# Half_bridge_drivers.net
KiCad netlist of a schematic drawn in Altium Designer
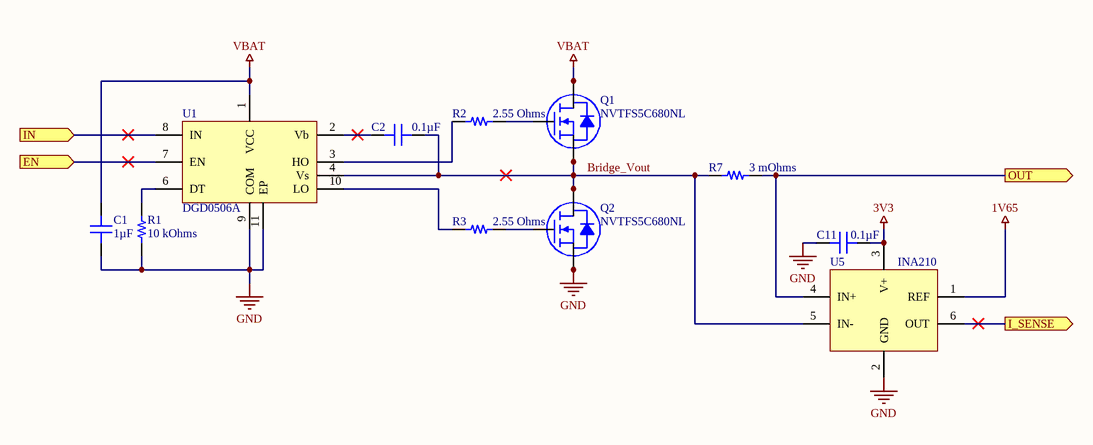
[diagram p0: Half_bridge_drivers.SchDoc]

(export (version "E")
  (design (tool "Eeschema 10.0.6"))
  (components
    (comp (ref "C1")
      (value "1µF")
      (footprint "CAP 0603_1608")
      (description "CAP CER 1UF 25V X7R 0603")
      (fields
        (field (name "PART NUMBER") "GCJ188R71E105KA01D")
        (field (name "MANUFACTURER") "Murata Electronics")
      )
      (libsource (lib "Celestial Altium Library - altium_library") (part "Capacitor"))
    )
    (comp (ref "C2")
      (value "0.1µF")
      (footprint "CAP 0603_1608")
      (description "CAP CER 0.1UF 100V 0603 EPOXY")
      (fields
        (field (name "PART NUMBER") "GCG188R92A104KA03D")
        (field (name "MANUFACTURER") "Murata Electronics")
      )
      (libsource (lib "Celestial Altium Library - altium_library") (part "Capacitor"))
    )
    (comp (ref "C11")
      (value "0.1µF")
      (footprint "CAP 0603_1608")
      (description "CAP CER 0.1UF 100V 0603 EPOXY")
      (fields
        (field (name "PART NUMBER") "GCG188R92A104KA03D")
        (field (name "MANUFACTURER") "Murata Electronics")
      )
      (libsource (lib "Celestial Altium Library - altium_library") (part "Capacitor"))
    )
    (comp (ref "Q1")
      (value "NVTFS5C680NL")
      (footprint "NVTFS015N04CTAG")
      (libsource (lib "IC") (part "NVTFS5C680NL"))
    )
    (comp (ref "Q2")
      (value "NVTFS5C680NL")
      (footprint "NVTFS015N04CTAG")
      (libsource (lib "IC") (part "NVTFS5C680NL"))
    )
    (comp (ref "R1")
      (value "10 kOhms")
      (footprint "RES 0603_1608")
      (description "RES 10K OHM 0.1% 1/16W 0603")
      (fields
        (field (name "PART NUMBER") "RNCS0603BKE10K0")
        (field (name "MANUFACTURER") "Stackpole Electronics Inc")
      )
      (libsource (lib "Celestial Altium Library - altium_library") (part "Resistor"))
    )
    (comp (ref "R2")
      (value "2.55 Ohms")
      (footprint "RES 0603_1608")
      (description "RES SMD 2.55 OHM 1% 1/10W 0603")
      (fields (field (name "PART NUMBER") "CRCW06032R55FKEA") (field (name "MANUFACTURER") "Vishay Dale"))
      (libsource (lib "Celestial Altium Library - altium_library") (part "Resistor"))
    )
    (comp (ref "R3")
      (value "2.55 Ohms")
      (footprint "RES 0603_1608")
      (description "RES SMD 2.55 OHM 1% 1/10W 0603")
      (fields (field (name "PART NUMBER") "CRCW06032R55FKEA") (field (name "MANUFACTURER") "Vishay Dale"))
      (libsource (lib "Celestial Altium Library - altium_library") (part "Resistor"))
    )
    (comp (ref "R7")
      (value "3 mOhms")
      (footprint "STACKPOLE CSR0603")
      (description "RES SHUNT, 0603, 0.003 OHM, 1%,")
      (fields
        (field (name "PART NUMBER") "CSS0603FT3L00")
        (field (name "MANUFACTURER") "Stackpole Electronics Inc")
      )
      (libsource (lib "Celestial Altium Library - altium_library") (part "Resistor"))
    )
    (comp (ref "U1")
      (value "DGD0506A")
      (footprint "10-WDFN3030")
      (description "Half Bridge driver - N FET")
      (libsource (lib "IC") (part "DGD0506A"))
    )
    (comp (ref "U5")
      (value "INA210")
      (footprint "TI SC70-6 DCK")
      (description "Current sense amplifier")
      (libsource (lib "IC") (part "INA210"))
    )
  )
  (nets
    (net (code "1") (name "/Bridge_Vout") (class "Default")
      (node (ref "C2") (pin "1") (pinfunction "1_1") (pintype "passive"))
      (node (ref "Q1") (pin "1") (pinfunction "S_1") (pintype "passive"))
      (node (ref "Q1") (pin "2") (pinfunction "S_2") (pintype "passive"))
      (node (ref "Q1") (pin "3") (pinfunction "S_3") (pintype "passive"))
      (node (ref "Q2") (pin "5") (pinfunction "D_5") (pintype "passive"))
      (node (ref "Q2") (pin "6") (pinfunction "D_6") (pintype "passive"))
      (node (ref "Q2") (pin "7") (pinfunction "D_7") (pintype "passive"))
      (node (ref "Q2") (pin "8") (pinfunction "D_8") (pintype "passive"))
      (node (ref "R7") (pin "1") (pinfunction "1_1") (pintype "passive"))
      (node (ref "U1") (pin "4") (pinfunction "Vs_4") (pintype "passive"))
      (node (ref "U5") (pin "5") (pinfunction "IN-_5") (pintype "passive"))
    )
    (net (code "2") (name "/EN") (class "Default")
      (node (ref "U1") (pin "7") (pinfunction "EN_7") (pintype "passive"))
    )
    (net (code "3") (name "/IN") (class "Default")
      (node (ref "U1") (pin "8") (pinfunction "IN_8") (pintype "passive"))
    )
    (net (code "4") (name "/I_SENSE") (class "Default")
      (node (ref "U5") (pin "6") (pinfunction "OUT_6") (pintype "passive"))
    )
    (net (code "5") (name "/OUT") (class "Default")
      (node (ref "R7") (pin "2") (pinfunction "2_2") (pintype "passive"))
      (node (ref "U5") (pin "4") (pinfunction "IN+_4") (pintype "passive"))
    )
    (net (code "6") (name "1V65") (class "Default")
      (node (ref "U5") (pin "1") (pinfunction "REF_1") (pintype "passive"))
    )
    (net (code "7") (name "3V3") (class "Default")
      (node (ref "C11") (pin "2") (pinfunction "2_2") (pintype "passive"))
      (node (ref "U5") (pin "3") (pinfunction "V+_3") (pintype "passive"))
    )
    (net (code "8") (name "GND") (class "Default")
      (node (ref "C1") (pin "1") (pinfunction "1_1") (pintype "passive"))
      (node (ref "C11") (pin "1") (pinfunction "1_1") (pintype "passive"))
      (node (ref "Q2") (pin "1") (pinfunction "S_1") (pintype "passive"))
      (node (ref "Q2") (pin "2") (pinfunction "S_2") (pintype "passive"))
      (node (ref "Q2") (pin "3") (pinfunction "S_3") (pintype "passive"))
      (node (ref "R1") (pin "2") (pinfunction "2_2") (pintype "passive"))
      (node (ref "U1") (pin "11") (pinfunction "EP_11") (pintype "passive"))
      (node (ref "U1") (pin "9") (pinfunction "COM_9") (pintype "passive"))
      (node (ref "U5") (pin "2") (pinfunction "GND_2") (pintype "passive"))
    )
    (net (code "9") (name "Net-(Q1-G)") (class "Default")
      (node (ref "Q1") (pin "4") (pinfunction "G_4") (pintype "passive"))
      (node (ref "R2") (pin "2") (pinfunction "2_2") (pintype "passive"))
    )
    (net (code "10") (name "Net-(Q2-G)") (class "Default")
      (node (ref "Q2") (pin "4") (pinfunction "G_4") (pintype "passive"))
      (node (ref "R3") (pin "2") (pinfunction "2_2") (pintype "passive"))
    )
    (net (code "11") (name "Net-(U1-DT)") (class "Default")
      (node (ref "R1") (pin "1") (pinfunction "1_1") (pintype "passive"))
      (node (ref "U1") (pin "6") (pinfunction "DT_6") (pintype "passive"))
    )
    (net (code "12") (name "Net-(U1-HO)") (class "Default")
      (node (ref "R2") (pin "1") (pinfunction "1_1") (pintype "passive"))
      (node (ref "U1") (pin "3") (pinfunction "HO_3") (pintype "passive"))
    )
    (net (code "13") (name "Net-(U1-LO)") (class "Default")
      (node (ref "R3") (pin "1") (pinfunction "1_1") (pintype "passive"))
      (node (ref "U1") (pin "10") (pinfunction "LO_10") (pintype "passive"))
    )
    (net (code "14") (name "Net-(U1-Vb)") (class "Default")
      (node (ref "C2") (pin "2") (pinfunction "2_2") (pintype "passive"))
      (node (ref "U1") (pin "2") (pinfunction "Vb_2") (pintype "passive"))
    )
    (net (code "15") (name "VBAT") (class "Default")
      (node (ref "C1") (pin "2") (pinfunction "2_2") (pintype "passive"))
      (node (ref "Q1") (pin "5") (pinfunction "D_5") (pintype "passive"))
      (node (ref "Q1") (pin "6") (pinfunction "D_6") (pintype "passive"))
      (node (ref "Q1") (pin "7") (pinfunction "D_7") (pintype "passive"))
      (node (ref "Q1") (pin "8") (pinfunction "D_8") (pintype "passive"))
      (node (ref "U1") (pin "1") (pinfunction "VCC_1") (pintype "passive"))
    )
  )
)
